# 7g_-_Current_FB_Protection.net
KiCad netlist of a schematic drawn in Altium Designer
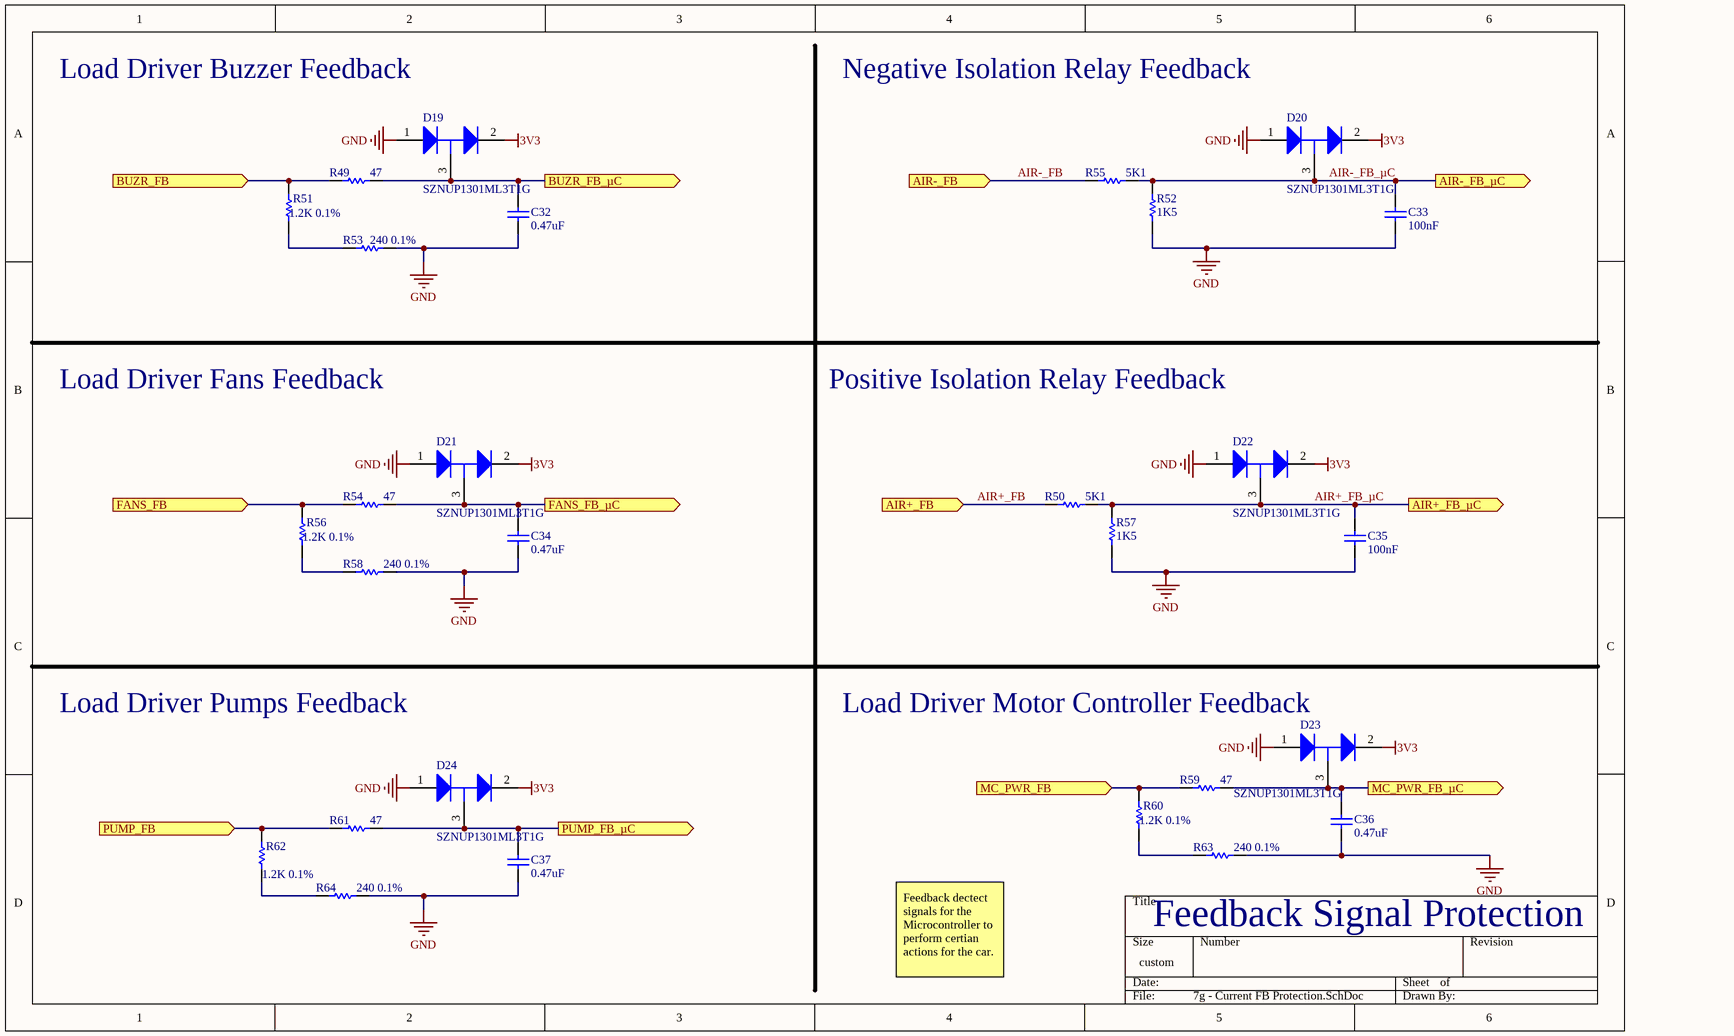
[diagram p0: 7g - Current FB Protection.SchDoc]

(export (version "E")
  (design (tool "Eeschema 10.0.6"))
  (components
    (comp (ref "C32")
      (value "0.47uF")
      (footprint "1608[0603]")
      (description "Capacitor")
      (fields (field (name "Comment") "Cap") (field (name "PUBLISHER") "Altium Limited"))
      (libsource (lib "Miscellaneous Devices") (part "Cap"))
    )
    (comp (ref "C33")
      (value "100nF")
      (footprint "1608[0603]")
      (description "Capacitor")
      (fields (field (name "Comment") "Cap") (field (name "PUBLISHER") "Altium Limited"))
      (libsource (lib "Miscellaneous Devices") (part "Cap"))
    )
    (comp (ref "C34")
      (value "0.47uF")
      (footprint "1608[0603]")
      (description "Capacitor")
      (fields (field (name "Comment") "Cap") (field (name "PUBLISHER") "Altium Limited"))
      (libsource (lib "Miscellaneous Devices") (part "Cap"))
    )
    (comp (ref "C35")
      (value "100nF")
      (footprint "1608[0603]")
      (description "Capacitor")
      (fields (field (name "Comment") "Cap") (field (name "PUBLISHER") "Altium Limited"))
      (libsource (lib "Miscellaneous Devices") (part "Cap"))
    )
    (comp (ref "C36")
      (value "0.47uF")
      (footprint "1608[0603]")
      (description "Capacitor")
      (fields (field (name "Comment") "Cap") (field (name "PUBLISHER") "Altium Limited"))
      (libsource (lib "Miscellaneous Devices") (part "Cap"))
    )
    (comp (ref "C37")
      (value "0.47uF")
      (footprint "1608[0603]")
      (description "Capacitor")
      (fields (field (name "Comment") "Cap") (field (name "PUBLISHER") "Altium Limited"))
      (libsource (lib "Miscellaneous Devices") (part "Cap"))
    )
    (comp (ref "D19")
      (value "SZNUP1301ML3T1G")
      (footprint "ONSC-SOT-23-3-318-08_V")
      (fields (field (name "MANUFACTURER") "On Semiconductor"))
      (libsource (lib "Altium Content Vault") (part "ONSC-NUP1301-SOT-23-3-318-08"))
    )
    (comp (ref "D20")
      (value "SZNUP1301ML3T1G")
      (footprint "ONSC-SOT-23-3-318-08_V")
      (fields (field (name "MANUFACTURER") "On Semiconductor"))
      (libsource (lib "Altium Content Vault") (part "ONSC-NUP1301-SOT-23-3-318-08"))
    )
    (comp (ref "D21")
      (value "SZNUP1301ML3T1G")
      (footprint "ONSC-SOT-23-3-318-08_V")
      (fields (field (name "MANUFACTURER") "On Semiconductor"))
      (libsource (lib "Altium Content Vault") (part "ONSC-NUP1301-SOT-23-3-318-08"))
    )
    (comp (ref "D22")
      (value "SZNUP1301ML3T1G")
      (footprint "ONSC-SOT-23-3-318-08_V")
      (fields (field (name "MANUFACTURER") "On Semiconductor"))
      (libsource (lib "Altium Content Vault") (part "ONSC-NUP1301-SOT-23-3-318-08"))
    )
    (comp (ref "D23")
      (value "SZNUP1301ML3T1G")
      (footprint "ONSC-SOT-23-3-318-08_V")
      (fields (field (name "MANUFACTURER") "On Semiconductor"))
      (libsource (lib "Altium Content Vault") (part "ONSC-NUP1301-SOT-23-3-318-08"))
    )
    (comp (ref "D24")
      (value "SZNUP1301ML3T1G")
      (footprint "ONSC-SOT-23-3-318-08_V")
      (fields (field (name "MANUFACTURER") "On Semiconductor"))
      (libsource (lib "Altium Content Vault") (part "ONSC-NUP1301-SOT-23-3-318-08"))
    )
    (comp (ref "R49")
      (value "47")
      (footprint "1608[0603]")
      (description "Resistor")
      (fields (field (name "Comment") "Res1") (field (name "PUBLISHER") "Altium Limited"))
      (libsource (lib "Miscellaneous Devices") (part "Res1"))
    )
    (comp (ref "R50")
      (value "5K1")
      (footprint "1608[0603]")
      (description "Resistor")
      (fields (field (name "Comment") "Res1") (field (name "PUBLISHER") "Altium Limited"))
      (libsource (lib "Miscellaneous Devices") (part "Res1"))
    )
    (comp (ref "R51")
      (value "1.2K 0.1%")
      (footprint "1608[0603]")
      (description "Resistor")
      (fields (field (name "Comment") "Res1") (field (name "PUBLISHER") "Altium Limited"))
      (libsource (lib "Miscellaneous Devices") (part "Res1"))
    )
    (comp (ref "R52")
      (value "1K5")
      (footprint "1608[0603]")
      (description "Resistor")
      (fields (field (name "Comment") "Res1") (field (name "PUBLISHER") "Altium Limited"))
      (libsource (lib "Miscellaneous Devices") (part "Res1"))
    )
    (comp (ref "R53")
      (value "240 0.1%")
      (footprint "1608[0603]")
      (description "Resistor")
      (fields (field (name "Comment") "Res1") (field (name "PUBLISHER") "Altium Limited"))
      (libsource (lib "Miscellaneous Devices") (part "Res1"))
    )
    (comp (ref "R54")
      (value "47")
      (footprint "1608[0603]")
      (description "Resistor")
      (fields (field (name "Comment") "Res1") (field (name "PUBLISHER") "Altium Limited"))
      (libsource (lib "Miscellaneous Devices") (part "Res1"))
    )
    (comp (ref "R55")
      (value "5K1")
      (footprint "1608[0603]")
      (description "Resistor")
      (fields (field (name "Comment") "Res1") (field (name "PUBLISHER") "Altium Limited"))
      (libsource (lib "Miscellaneous Devices") (part "Res1"))
    )
    (comp (ref "R56")
      (value "1.2K 0.1%")
      (footprint "1608[0603]")
      (description "Resistor")
      (fields (field (name "Comment") "Res1") (field (name "PUBLISHER") "Altium Limited"))
      (libsource (lib "Miscellaneous Devices") (part "Res1"))
    )
    (comp (ref "R57")
      (value "1K5")
      (footprint "1608[0603]")
      (description "Resistor")
      (fields (field (name "Comment") "Res1") (field (name "PUBLISHER") "Altium Limited"))
      (libsource (lib "Miscellaneous Devices") (part "Res1"))
    )
    (comp (ref "R58")
      (value "240 0.1%")
      (footprint "1608[0603]")
      (description "Resistor")
      (fields (field (name "Comment") "Res1") (field (name "PUBLISHER") "Altium Limited"))
      (libsource (lib "Miscellaneous Devices") (part "Res1"))
    )
    (comp (ref "R59")
      (value "47")
      (footprint "1608[0603]")
      (description "Resistor")
      (fields (field (name "Comment") "Res1") (field (name "PUBLISHER") "Altium Limited"))
      (libsource (lib "Miscellaneous Devices") (part "Res1"))
    )
    (comp (ref "R60")
      (value "1.2K 0.1%")
      (footprint "1608[0603]")
      (description "Resistor")
      (fields (field (name "Comment") "Res1") (field (name "PUBLISHER") "Altium Limited"))
      (libsource (lib "Miscellaneous Devices") (part "Res1"))
    )
    (comp (ref "R61")
      (value "47")
      (footprint "1608[0603]")
      (description "Resistor")
      (fields (field (name "Comment") "Res1") (field (name "PUBLISHER") "Altium Limited"))
      (libsource (lib "Miscellaneous Devices") (part "Res1"))
    )
    (comp (ref "R62")
      (value "1.2K 0.1%")
      (footprint "1608[0603]")
      (description "Resistor")
      (fields (field (name "Comment") "Res1") (field (name "PUBLISHER") "Altium Limited"))
      (libsource (lib "Miscellaneous Devices") (part "Res1"))
    )
    (comp (ref "R63")
      (value "240 0.1%")
      (footprint "1608[0603]")
      (description "Resistor")
      (fields (field (name "Comment") "Res1") (field (name "PUBLISHER") "Altium Limited"))
      (libsource (lib "Miscellaneous Devices") (part "Res1"))
    )
    (comp (ref "R64")
      (value "240 0.1%")
      (footprint "1608[0603]")
      (description "Resistor")
      (fields (field (name "Comment") "Res1") (field (name "PUBLISHER") "Altium Limited"))
      (libsource (lib "Miscellaneous Devices") (part "Res1"))
    )
  )
  (nets
    (net (code "1") (name "/AIR+_FB") (class "Default")
      (node (ref "R50") (pin "1") (pinfunction "1_1") (pintype "passive"))
    )
    (net (code "2") (name "/AIR+_FB_µC") (class "Default")
      (node (ref "C35") (pin "2") (pinfunction "2_2") (pintype "passive"))
      (node (ref "D22") (pin "3") (pinfunction "K/A_3") (pintype "passive"))
      (node (ref "R50") (pin "2") (pinfunction "2_2") (pintype "passive"))
      (node (ref "R57") (pin "2") (pinfunction "2_2") (pintype "passive"))
    )
    (net (code "3") (name "/AIR-_FB") (class "Default")
      (node (ref "R55") (pin "1") (pinfunction "1_1") (pintype "passive"))
    )
    (net (code "4") (name "/AIR-_FB_µC") (class "Default")
      (node (ref "C33") (pin "2") (pinfunction "2_2") (pintype "passive"))
      (node (ref "D20") (pin "3") (pinfunction "K/A_3") (pintype "passive"))
      (node (ref "R52") (pin "2") (pinfunction "2_2") (pintype "passive"))
      (node (ref "R55") (pin "2") (pinfunction "2_2") (pintype "passive"))
    )
    (net (code "5") (name "/BUZR_FB") (class "Default")
      (node (ref "R49") (pin "1") (pinfunction "1_1") (pintype "passive"))
      (node (ref "R51") (pin "2") (pinfunction "2_2") (pintype "passive"))
    )
    (net (code "6") (name "/BUZR_FB_µC") (class "Default")
      (node (ref "C32") (pin "2") (pinfunction "2_2") (pintype "passive"))
      (node (ref "D19") (pin "3") (pinfunction "K/A_3") (pintype "passive"))
      (node (ref "R49") (pin "2") (pinfunction "2_2") (pintype "passive"))
    )
    (net (code "7") (name "/FANS_FB") (class "Default")
      (node (ref "R54") (pin "1") (pinfunction "1_1") (pintype "passive"))
      (node (ref "R56") (pin "2") (pinfunction "2_2") (pintype "passive"))
    )
    (net (code "8") (name "/FANS_FB_µC") (class "Default")
      (node (ref "C34") (pin "2") (pinfunction "2_2") (pintype "passive"))
      (node (ref "D21") (pin "3") (pinfunction "K/A_3") (pintype "passive"))
      (node (ref "R54") (pin "2") (pinfunction "2_2") (pintype "passive"))
    )
    (net (code "9") (name "/MC_PWR_FB") (class "Default")
      (node (ref "R59") (pin "1") (pinfunction "1_1") (pintype "passive"))
      (node (ref "R60") (pin "2") (pinfunction "2_2") (pintype "passive"))
    )
    (net (code "10") (name "/MC_PWR_FB_µC") (class "Default")
      (node (ref "C36") (pin "2") (pinfunction "2_2") (pintype "passive"))
      (node (ref "D23") (pin "3") (pinfunction "K/A_3") (pintype "passive"))
      (node (ref "R59") (pin "2") (pinfunction "2_2") (pintype "passive"))
    )
    (net (code "11") (name "/PUMP_FB") (class "Default")
      (node (ref "R61") (pin "1") (pinfunction "1_1") (pintype "passive"))
      (node (ref "R62") (pin "2") (pinfunction "2_2") (pintype "passive"))
    )
    (net (code "12") (name "/PUMP_FB_µC") (class "Default")
      (node (ref "C37") (pin "2") (pinfunction "2_2") (pintype "passive"))
      (node (ref "D24") (pin "3") (pinfunction "K/A_3") (pintype "passive"))
      (node (ref "R61") (pin "2") (pinfunction "2_2") (pintype "passive"))
    )
    (net (code "13") (name "3V3") (class "Default")
      (node (ref "D19") (pin "2") (pinfunction "K_2") (pintype "passive"))
      (node (ref "D20") (pin "2") (pinfunction "K_2") (pintype "passive"))
      (node (ref "D21") (pin "2") (pinfunction "K_2") (pintype "passive"))
      (node (ref "D22") (pin "2") (pinfunction "K_2") (pintype "passive"))
      (node (ref "D23") (pin "2") (pinfunction "K_2") (pintype "passive"))
      (node (ref "D24") (pin "2") (pinfunction "K_2") (pintype "passive"))
    )
    (net (code "14") (name "GND") (class "Default")
      (node (ref "C32") (pin "1") (pinfunction "1_1") (pintype "passive"))
      (node (ref "C33") (pin "1") (pinfunction "1_1") (pintype "passive"))
      (node (ref "C34") (pin "1") (pinfunction "1_1") (pintype "passive"))
      (node (ref "C35") (pin "1") (pinfunction "1_1") (pintype "passive"))
      (node (ref "C36") (pin "1") (pinfunction "1_1") (pintype "passive"))
      (node (ref "C37") (pin "1") (pinfunction "1_1") (pintype "passive"))
      (node (ref "D19") (pin "1") (pinfunction "A_1") (pintype "passive"))
      (node (ref "D20") (pin "1") (pinfunction "A_1") (pintype "passive"))
      (node (ref "D21") (pin "1") (pinfunction "A_1") (pintype "passive"))
      (node (ref "D22") (pin "1") (pinfunction "A_1") (pintype "passive"))
      (node (ref "D23") (pin "1") (pinfunction "A_1") (pintype "passive"))
      (node (ref "D24") (pin "1") (pinfunction "A_1") (pintype "passive"))
      (node (ref "R52") (pin "1") (pinfunction "1_1") (pintype "passive"))
      (node (ref "R53") (pin "2") (pinfunction "2_2") (pintype "passive"))
      (node (ref "R57") (pin "1") (pinfunction "1_1") (pintype "passive"))
      (node (ref "R58") (pin "2") (pinfunction "2_2") (pintype "passive"))
      (node (ref "R63") (pin "2") (pinfunction "2_2") (pintype "passive"))
      (node (ref "R64") (pin "2") (pinfunction "2_2") (pintype "passive"))
    )
    (net (code "15") (name "Net-(R51-Pad1)") (class "Default")
      (node (ref "R51") (pin "1") (pinfunction "1_1") (pintype "passive"))
      (node (ref "R53") (pin "1") (pinfunction "1_1") (pintype "passive"))
    )
    (net (code "16") (name "Net-(R56-Pad1)") (class "Default")
      (node (ref "R56") (pin "1") (pinfunction "1_1") (pintype "passive"))
      (node (ref "R58") (pin "1") (pinfunction "1_1") (pintype "passive"))
    )
    (net (code "17") (name "Net-(R60-Pad1)") (class "Default")
      (node (ref "R60") (pin "1") (pinfunction "1_1") (pintype "passive"))
      (node (ref "R63") (pin "1") (pinfunction "1_1") (pintype "passive"))
    )
    (net (code "18") (name "Net-(R62-Pad1)") (class "Default")
      (node (ref "R62") (pin "1") (pinfunction "1_1") (pintype "passive"))
      (node (ref "R64") (pin "1") (pinfunction "1_1") (pintype "passive"))
    )
  )
)
